# imu.net
KiCad netlist of a schematic drawn in Altium Designer
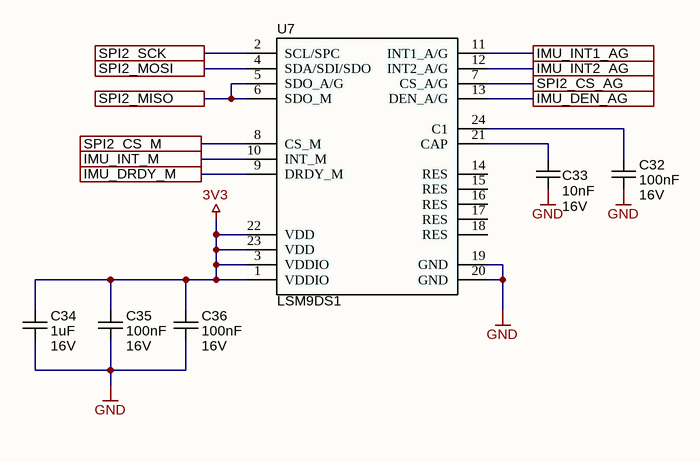
[diagram p0: imu.SchDoc]

(export (version "E")
  (design (tool "Eeschema 10.0.6"))
  (components
    (comp (ref "C32")
      (value "100nF")
      (footprint "C0603")
      (fields (field (name "VOLTAGE") "16V") (field (name "Comment") "C0603"))
      (libsource (lib "DZ_LIB") (part "C0603"))
    )
    (comp (ref "C33")
      (value "10nF")
      (footprint "C0603")
      (fields (field (name "VOLTAGE") "16V") (field (name "Comment") "C0603"))
      (libsource (lib "DZ_LIB") (part "C0603"))
    )
    (comp (ref "C34")
      (value "1uF")
      (footprint "C0603")
      (fields (field (name "VOLTAGE") "16V") (field (name "Comment") "C0603"))
      (libsource (lib "DZ_LIB") (part "C0603"))
    )
    (comp (ref "C35")
      (value "100nF")
      (footprint "C0603")
      (fields (field (name "VOLTAGE") "16V") (field (name "Comment") "C0603"))
      (libsource (lib "DZ_LIB") (part "C0603"))
    )
    (comp (ref "C36")
      (value "100nF")
      (footprint "C0603")
      (fields (field (name "VOLTAGE") "16V") (field (name "Comment") "C0603"))
      (libsource (lib "DZ_LIB") (part "C0603"))
    )
    (comp (ref "U7")
      (value "LSM9DS1")
      (footprint "STM-LGA-24_3500X3000X1000")
      (libsource (lib "DZ_LIB") (part "STM-LSM9DS1-24"))
    )
  )
  (nets
    (net (code "1") (name "/IMU_DEN_AG") (class "Default")
      (node (ref "U7") (pin "13") (pinfunction "DEN_A/G_13") (pintype "passive"))
    )
    (net (code "2") (name "/IMU_DRDY_M") (class "Default")
      (node (ref "U7") (pin "9") (pinfunction "DRDY_M_9") (pintype "passive"))
    )
    (net (code "3") (name "/IMU_INT1_AG") (class "Default")
      (node (ref "U7") (pin "11") (pinfunction "INT1_A/G_11") (pintype "passive"))
    )
    (net (code "4") (name "/IMU_INT2_AG") (class "Default")
      (node (ref "U7") (pin "12") (pinfunction "INT2_A/G_12") (pintype "passive"))
    )
    (net (code "5") (name "/IMU_INT_M") (class "Default")
      (node (ref "U7") (pin "10") (pinfunction "INT_M_10") (pintype "passive"))
    )
    (net (code "6") (name "/SPI2_CS_AG") (class "Default")
      (node (ref "U7") (pin "7") (pinfunction "CS_A/G_7") (pintype "passive"))
    )
    (net (code "7") (name "/SPI2_CS_M") (class "Default")
      (node (ref "U7") (pin "8") (pinfunction "CS_M_8") (pintype "passive"))
    )
    (net (code "8") (name "/SPI2_MISO") (class "Default")
      (node (ref "U7") (pin "5") (pinfunction "SDO_A/G_5") (pintype "passive"))
      (node (ref "U7") (pin "6") (pinfunction "SDO_M_6") (pintype "passive"))
    )
    (net (code "9") (name "/SPI2_MOSI") (class "Default")
      (node (ref "U7") (pin "4") (pinfunction "SDA/SDI/SDO_4") (pintype "passive"))
    )
    (net (code "10") (name "/SPI2_SCK") (class "Default")
      (node (ref "U7") (pin "2") (pinfunction "SCL/SPC_2") (pintype "passive"))
    )
    (net (code "11") (name "3V3") (class "Default")
      (node (ref "C34") (pin "1") (pinfunction "1_1") (pintype "passive"))
      (node (ref "C35") (pin "1") (pinfunction "1_1") (pintype "passive"))
      (node (ref "C36") (pin "1") (pinfunction "1_1") (pintype "passive"))
      (node (ref "U7") (pin "1") (pinfunction "VDDIO_1") (pintype "passive"))
      (node (ref "U7") (pin "22") (pinfunction "VDD_22") (pintype "passive"))
      (node (ref "U7") (pin "23") (pinfunction "VDD_23") (pintype "passive"))
      (node (ref "U7") (pin "3") (pinfunction "VDDIO_3") (pintype "passive"))
    )
    (net (code "12") (name "GND") (class "Default")
      (node (ref "C32") (pin "2") (pinfunction "2_2") (pintype "passive"))
      (node (ref "C33") (pin "1") (pinfunction "1_1") (pintype "passive"))
      (node (ref "C34") (pin "2") (pinfunction "2_2") (pintype "passive"))
      (node (ref "C35") (pin "2") (pinfunction "2_2") (pintype "passive"))
      (node (ref "C36") (pin "2") (pinfunction "2_2") (pintype "passive"))
      (node (ref "U7") (pin "19") (pinfunction "GND_19") (pintype "passive"))
      (node (ref "U7") (pin "20") (pinfunction "GND_20") (pintype "passive"))
    )
    (net (code "13") (name "Net-(U7-C1)") (class "Default")
      (node (ref "C32") (pin "1") (pinfunction "1_1") (pintype "passive"))
      (node (ref "U7") (pin "24") (pinfunction "C1_24") (pintype "passive"))
    )
    (net (code "14") (name "Net-(U7-CAP)") (class "Default")
      (node (ref "C33") (pin "2") (pinfunction "2_2") (pintype "passive"))
      (node (ref "U7") (pin "21") (pinfunction "CAP_21") (pintype "passive"))
    )
    (net (code "15") (name "unconnected-(U7-RES-Pad14)") (class "Default")
      (node (ref "U7") (pin "14") (pinfunction "RES_14") (pintype "passive"))
    )
    (net (code "16") (name "unconnected-(U7-RES-Pad15)") (class "Default")
      (node (ref "U7") (pin "15") (pinfunction "RES_15") (pintype "passive"))
    )
    (net (code "17") (name "unconnected-(U7-RES-Pad16)") (class "Default")
      (node (ref "U7") (pin "16") (pinfunction "RES_16") (pintype "passive"))
    )
    (net (code "18") (name "unconnected-(U7-RES-Pad17)") (class "Default")
      (node (ref "U7") (pin "17") (pinfunction "RES_17") (pintype "passive"))
    )
    (net (code "19") (name "unconnected-(U7-RES-Pad18)") (class "Default")
      (node (ref "U7") (pin "18") (pinfunction "RES_18") (pintype "passive"))
    )
  )
)
